# Nanite_85_micro-b_v1_0.net
KiCad netlist of a schematic drawn in EAGLE
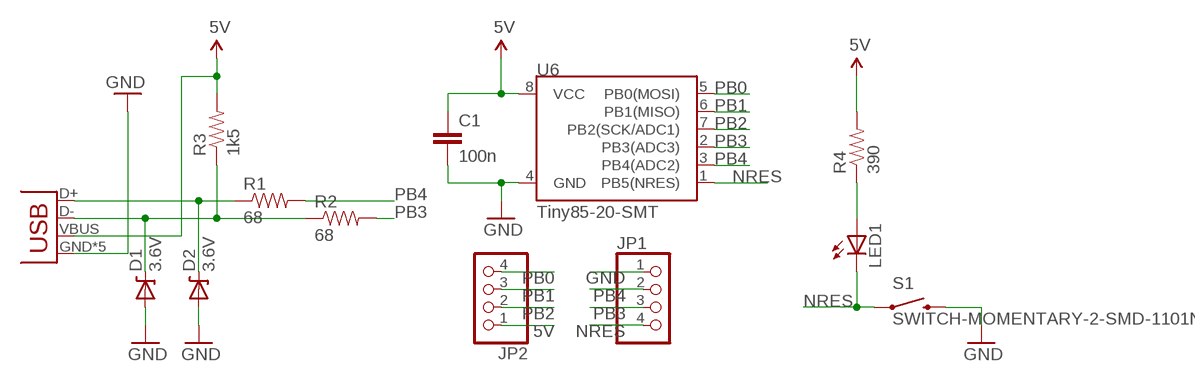
[diagram p0: schematic, sheet 1]

(export (version "E")
  (design (tool "Eeschema 10.0.6"))
  (components
    (comp (ref "C1")
      (value "100n")
      (footprint "eagle-import:0805")
      (libsource (lib "eagle-import") (part "CAP0805"))
    )
    (comp (ref "D1")
      (value "3.6V")
      (footprint "eagle-import:SOD-323")
      (libsource (lib "eagle-import") (part "DIODE-ZENER-BZT52"))
    )
    (comp (ref "D2")
      (value "3.6V")
      (footprint "eagle-import:SOD-323")
      (libsource (lib "eagle-import") (part "DIODE-ZENER-BZT52"))
    )
    (comp (ref "JP1")
      (value "HEADER-1X4ROUND")
      (footprint "eagle-import:1X04_ROUND")
      (libsource (lib "eagle-import") (part "HEADER-1X4ROUND"))
    )
    (comp (ref "JP2")
      (value "HEADER-1X4ROUND")
      (footprint "eagle-import:1X04_ROUND")
      (libsource (lib "eagle-import") (part "HEADER-1X4ROUND"))
    )
    (comp (ref "JP4")
      (value "USB-MICROB-HOLE-ALLCONNECTED")
      (footprint "eagle-import:USB-MICROB-HOLES")
      (libsource (lib "eagle-import") (part "USB-MICROB-HOLE-ALLCONNECTED"))
    )
    (comp (ref "LED1")
      (value "LEDCHIPLED_0805")
      (footprint "eagle-import:CHIPLED_0805")
      (libsource (lib "eagle-import") (part "LEDCHIPLED_0805"))
    )
    (comp (ref "R1")
      (value "68")
      (footprint "eagle-import:0805")
      (libsource (lib "eagle-import") (part "RESISTOR0805-RES"))
    )
    (comp (ref "R2")
      (value "68")
      (footprint "eagle-import:0805")
      (libsource (lib "eagle-import") (part "RESISTOR0805-RES"))
    )
    (comp (ref "R3")
      (value "1k5")
      (footprint "eagle-import:0805")
      (libsource (lib "eagle-import") (part "RESISTOR0805-RES"))
    )
    (comp (ref "R4")
      (value "390")
      (footprint "eagle-import:0805")
      (libsource (lib "eagle-import") (part "RESISTOR0805-RES"))
    )
    (comp (ref "S1")
      (value "SWITCH-MOMENTARY-2-SMD-1101NE")
      (footprint "eagle-import:TACTILE-SWITCH-1101NE")
      (libsource (lib "eagle-import") (part "SWITCH-MOMENTARY-2-SMD-1101NE"))
    )
    (comp (ref "U6")
      (value "Tiny85-20-SMT")
      (footprint "eagle-import:SO08-EIAJ")
      (libsource (lib "eagle-import") (part "ATTINY45TINY85-20-SMT"))
    )
  )
  (nets
    (net (code "1") (name "/NRES") (class "Default")
      (node (ref "JP1") (pin "4") (pinfunction "4_4") (pintype "passive"))
      (node (ref "LED1") (pin "C") (pinfunction "C_C") (pintype "passive"))
      (node (ref "S1") (pin "P$1") (pinfunction "1_P$1") (pintype "passive"))
      (node (ref "U6") (pin "1") (pinfunction "PB5(NRES)_1") (pintype "bidirectional"))
    )
    (net (code "2") (name "/PB0") (class "Default")
      (node (ref "JP2") (pin "4") (pinfunction "4_4") (pintype "passive"))
      (node (ref "U6") (pin "5") (pinfunction "PB0(MOSI)_5") (pintype "bidirectional"))
    )
    (net (code "3") (name "/PB1") (class "Default")
      (node (ref "JP2") (pin "3") (pinfunction "3_3") (pintype "passive"))
      (node (ref "U6") (pin "6") (pinfunction "PB1(MISO)_6") (pintype "bidirectional"))
    )
    (net (code "4") (name "/PB2") (class "Default")
      (node (ref "JP2") (pin "2") (pinfunction "2_2") (pintype "passive"))
      (node (ref "U6") (pin "7") (pinfunction "PB2(SCK/ADC1)_7") (pintype "bidirectional"))
    )
    (net (code "5") (name "/PB3") (class "Default")
      (node (ref "JP1") (pin "3") (pinfunction "3_3") (pintype "passive"))
      (node (ref "R2") (pin "2") (pinfunction "2_2") (pintype "passive"))
      (node (ref "U6") (pin "2") (pinfunction "PB3(ADC3)_2") (pintype "bidirectional"))
    )
    (net (code "6") (name "/PB4") (class "Default")
      (node (ref "JP1") (pin "2") (pinfunction "2_2") (pintype "passive"))
      (node (ref "R1") (pin "2") (pinfunction "2_2") (pintype "passive"))
      (node (ref "U6") (pin "3") (pinfunction "PB4(ADC2)_3") (pintype "bidirectional"))
    )
    (net (code "7") (name "5V") (class "Default")
      (node (ref "C1") (pin "1") (pinfunction "1_1") (pintype "passive"))
      (node (ref "JP2") (pin "1") (pinfunction "1_1") (pintype "passive"))
      (node (ref "JP4") (pin "VBUS") (pinfunction "VBUS_VBUS") (pintype "bidirectional"))
      (node (ref "R3") (pin "2") (pinfunction "2_2") (pintype "passive"))
      (node (ref "R4") (pin "2") (pinfunction "2_2") (pintype "passive"))
      (node (ref "U6") (pin "8") (pinfunction "VCC_8") (pintype "bidirectional"))
    )
    (net (code "8") (name "GND") (class "Default")
      (node (ref "C1") (pin "2") (pinfunction "2_2") (pintype "passive"))
      (node (ref "D1") (pin "2") (pinfunction "A_2") (pintype "passive"))
      (node (ref "D2") (pin "2") (pinfunction "A_2") (pintype "passive"))
      (node (ref "JP1") (pin "1") (pinfunction "1_1") (pintype "passive"))
      (node (ref "JP4") (pin "GND") (pinfunction "GND_GND") (pintype "bidirectional"))
      (node (ref "JP4") (pin "MT1") (pinfunction "GND_MT1") (pintype "bidirectional"))
      (node (ref "JP4") (pin "MT2") (pinfunction "GND_MT2") (pintype "bidirectional"))
      (node (ref "JP4") (pin "P$1") (pinfunction "GND_P$1") (pintype "bidirectional"))
      (node (ref "JP4") (pin "P$2") (pinfunction "GND_P$2") (pintype "bidirectional"))
      (node (ref "S1") (pin "P$2") (pinfunction "2_P$2") (pintype "passive"))
      (node (ref "U6") (pin "4") (pinfunction "GND_4") (pintype "bidirectional"))
    )
    (net (code "9") (name "Net-(D1-C)") (class "Default")
      (node (ref "D1") (pin "1") (pinfunction "C_1") (pintype "passive"))
      (node (ref "JP4") (pin "D-") (pinfunction "D-_D-") (pintype "bidirectional"))
      (node (ref "R2") (pin "1") (pinfunction "1_1") (pintype "passive"))
      (node (ref "R3") (pin "1") (pinfunction "1_1") (pintype "passive"))
    )
    (net (code "10") (name "Net-(D2-C)") (class "Default")
      (node (ref "D2") (pin "1") (pinfunction "C_1") (pintype "passive"))
      (node (ref "JP4") (pin "D+") (pinfunction "D+_D+") (pintype "bidirectional"))
      (node (ref "R1") (pin "1") (pinfunction "1_1") (pintype "passive"))
    )
    (net (code "11") (name "Net-(LED1-PadA)") (class "Default")
      (node (ref "LED1") (pin "A") (pinfunction "A_A") (pintype "passive"))
      (node (ref "R4") (pin "1") (pinfunction "1_1") (pintype "passive"))
    )
  )
)
